# lab4_schematic.net
KiCad netlist of a schematic drawn in Altium Designer
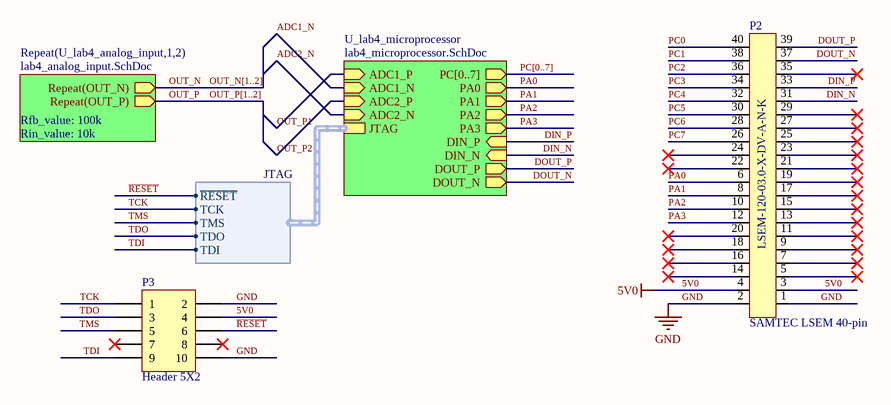
[diagram p0: lab4_schematic.SchDoc]

(export (version "E")
  (design (tool "Eeschema 10.0.6"))
  (components
    (comp (ref "P2")
      (value "SAMTEC LSEM 40-pin")
      (footprint "PcbLib_MW:LSEM-120-03.0-L-DV-A-N-K-TR")
      (fields (field (name "MANUFACTURER") "SAMTEC") (field (name "PART NUMBER") "LSEM-120-03.0-X-DV-A-N-K"))
      (libsource (lib "Schlib_MW") (part "LSEM-120-03.0-X-DV-A-N-K"))
    )
    (comp (ref "P3")
      (value "Header 5X2")
      (footprint "HDR2X5")
      (description "Header, 5-Pin, Dual row")
      (fields (field (name "PUBLISHER") "Altium Limited"))
      (libsource (lib "Miscellaneous Connectors") (part "Header 5X2"))
    )
  )
  (nets
    (net (code "6") (name "/DIN_N") (class "Default")
      (node (ref "P2") (pin "31") (pinfunction "16_31") (pintype "passive"))
    )
    (net (code "7") (name "/DIN_P") (class "Default")
      (node (ref "P2") (pin "33") (pinfunction "17_33") (pintype "passive"))
    )
    (net (code "8") (name "/DOUT_N") (class "Default")
      (node (ref "P2") (pin "37") (pinfunction "19_37") (pintype "passive"))
    )
    (net (code "9") (name "/DOUT_P") (class "Default")
      (node (ref "P2") (pin "39") (pinfunction "20_39") (pintype "passive"))
    )
    (net (code "16") (name "/PA0") (class "Default")
      (node (ref "P2") (pin "6") (pinfunction "4_6") (pintype "passive"))
    )
    (net (code "17") (name "/PA1") (class "Default")
      (node (ref "P2") (pin "8") (pinfunction "5_8") (pintype "passive"))
    )
    (net (code "18") (name "/PA2") (class "Default")
      (node (ref "P2") (pin "10") (pinfunction "6_10") (pintype "passive"))
    )
    (net (code "19") (name "/PA3") (class "Default")
      (node (ref "P2") (pin "12") (pinfunction "7_12") (pintype "passive"))
    )
    (net (code "20") (name "/PC0") (class "Default")
      (node (ref "P2") (pin "40") (pinfunction "21_40") (pintype "passive"))
    )
    (net (code "21") (name "/PC1") (class "Default")
      (node (ref "P2") (pin "38") (pinfunction "20_38") (pintype "passive"))
    )
    (net (code "22") (name "/PC2") (class "Default")
      (node (ref "P2") (pin "36") (pinfunction "19_36") (pintype "passive"))
    )
    (net (code "23") (name "/PC3") (class "Default")
      (node (ref "P2") (pin "34") (pinfunction "18_34") (pintype "passive"))
    )
    (net (code "24") (name "/PC4") (class "Default")
      (node (ref "P2") (pin "32") (pinfunction "17_32") (pintype "passive"))
    )
    (net (code "25") (name "/PC5") (class "Default")
      (node (ref "P2") (pin "30") (pinfunction "16_30") (pintype "passive"))
    )
    (net (code "26") (name "/PC6") (class "Default")
      (node (ref "P2") (pin "28") (pinfunction "15_28") (pintype "passive"))
    )
    (net (code "27") (name "/PC7") (class "Default")
      (node (ref "P2") (pin "26") (pinfunction "14_26") (pintype "passive"))
    )
    (net (code "29") (name "/TCK") (class "Default")
      (node (ref "P3") (pin "1") (pinfunction "1_1") (pintype "passive"))
    )
    (net (code "30") (name "/TDI") (class "Default")
      (node (ref "P3") (pin "9") (pinfunction "9_9") (pintype "passive"))
    )
    (net (code "31") (name "/TDO") (class "Default")
      (node (ref "P3") (pin "3") (pinfunction "3_3") (pintype "passive"))
    )
    (net (code "32") (name "/TMS") (class "Default")
      (node (ref "P3") (pin "5") (pinfunction "5_5") (pintype "passive"))
    )
    (net (code "34") (name "/~{RESET}") (class "Default")
      (node (ref "P3") (pin "6") (pinfunction "6_6") (pintype "passive"))
    )
    (net (code "35") (name "5V0") (class "Default")
      (node (ref "P2") (pin "3") (pinfunction "2_3") (pintype "passive"))
      (node (ref "P2") (pin "4") (pinfunction "3_4") (pintype "passive"))
      (node (ref "P3") (pin "4") (pinfunction "4_4") (pintype "passive"))
    )
    (net (code "36") (name "GND") (class "Default")
      (node (ref "P2") (pin "1") (pinfunction "1_1") (pintype "passive"))
      (node (ref "P2") (pin "2") (pinfunction "2_2") (pintype "passive"))
      (node (ref "P3") (pin "10") (pinfunction "10_10") (pintype "passive"))
      (node (ref "P3") (pin "2") (pinfunction "2_2") (pintype "passive"))
    )
    (net (code "37") (name "unconnected-(P2-3-Pad5)") (class "Default")
      (node (ref "P2") (pin "5") (pinfunction "3_5") (pintype "passive+no_connect"))
    )
    (net (code "38") (name "unconnected-(P2-4-Pad7)") (class "Default")
      (node (ref "P2") (pin "7") (pinfunction "4_7") (pintype "passive+no_connect"))
    )
    (net (code "39") (name "unconnected-(P2-5-Pad9)") (class "Default")
      (node (ref "P2") (pin "9") (pinfunction "5_9") (pintype "passive+no_connect"))
    )
    (net (code "40") (name "unconnected-(P2-6-Pad11)") (class "Default")
      (node (ref "P2") (pin "11") (pinfunction "6_11") (pintype "passive+no_connect"))
    )
    (net (code "41") (name "unconnected-(P2-7-Pad13)") (class "Default")
      (node (ref "P2") (pin "13") (pinfunction "7_13") (pintype "passive+no_connect"))
    )
    (net (code "42") (name "unconnected-(P2-8-Pad14)") (class "Default")
      (node (ref "P2") (pin "14") (pinfunction "8_14") (pintype "passive+no_connect"))
    )
    (net (code "43") (name "unconnected-(P2-8-Pad15)") (class "Default")
      (node (ref "P2") (pin "15") (pinfunction "8_15") (pintype "passive+no_connect"))
    )
    (net (code "44") (name "unconnected-(P2-9-Pad16)") (class "Default")
      (node (ref "P2") (pin "16") (pinfunction "9_16") (pintype "passive+no_connect"))
    )
    (net (code "45") (name "unconnected-(P2-9-Pad17)") (class "Default")
      (node (ref "P2") (pin "17") (pinfunction "9_17") (pintype "passive+no_connect"))
    )
    (net (code "46") (name "unconnected-(P2-10-Pad18)") (class "Default")
      (node (ref "P2") (pin "18") (pinfunction "10_18") (pintype "passive+no_connect"))
    )
    (net (code "47") (name "unconnected-(P2-10-Pad19)") (class "Default")
      (node (ref "P2") (pin "19") (pinfunction "10_19") (pintype "passive+no_connect"))
    )
    (net (code "48") (name "unconnected-(P2-11-Pad20)") (class "Default")
      (node (ref "P2") (pin "20") (pinfunction "11_20") (pintype "passive+no_connect"))
    )
    (net (code "49") (name "unconnected-(P2-11-Pad21)") (class "Default")
      (node (ref "P2") (pin "21") (pinfunction "11_21") (pintype "passive+no_connect"))
    )
    (net (code "50") (name "unconnected-(P2-12-Pad22)") (class "Default")
      (node (ref "P2") (pin "22") (pinfunction "12_22") (pintype "passive+no_connect"))
    )
    (net (code "51") (name "unconnected-(P2-12-Pad23)") (class "Default")
      (node (ref "P2") (pin "23") (pinfunction "12_23") (pintype "passive+no_connect"))
    )
    (net (code "52") (name "unconnected-(P2-13-Pad24)") (class "Default")
      (node (ref "P2") (pin "24") (pinfunction "13_24") (pintype "passive+no_connect"))
    )
    (net (code "53") (name "unconnected-(P2-13-Pad25)") (class "Default")
      (node (ref "P2") (pin "25") (pinfunction "13_25") (pintype "passive+no_connect"))
    )
    (net (code "54") (name "unconnected-(P2-14-Pad27)") (class "Default")
      (node (ref "P2") (pin "27") (pinfunction "14_27") (pintype "passive+no_connect"))
    )
    (net (code "55") (name "unconnected-(P2-15-Pad29)") (class "Default")
      (node (ref "P2") (pin "29") (pinfunction "15_29") (pintype "passive+no_connect"))
    )
    (net (code "56") (name "unconnected-(P2-18-Pad35)") (class "Default")
      (node (ref "P2") (pin "35") (pinfunction "18_35") (pintype "passive+no_connect"))
    )
    (net (code "57") (name "unconnected-(P3-Pad7)") (class "Default")
      (node (ref "P3") (pin "7") (pinfunction "7_7") (pintype "passive+no_connect"))
    )
    (net (code "58") (name "unconnected-(P3-Pad8)") (class "Default")
      (node (ref "P3") (pin "8") (pinfunction "8_8") (pintype "passive+no_connect"))
    )
  )
)
